# Power1.net
KiCad netlist of a schematic drawn in Altium Designer
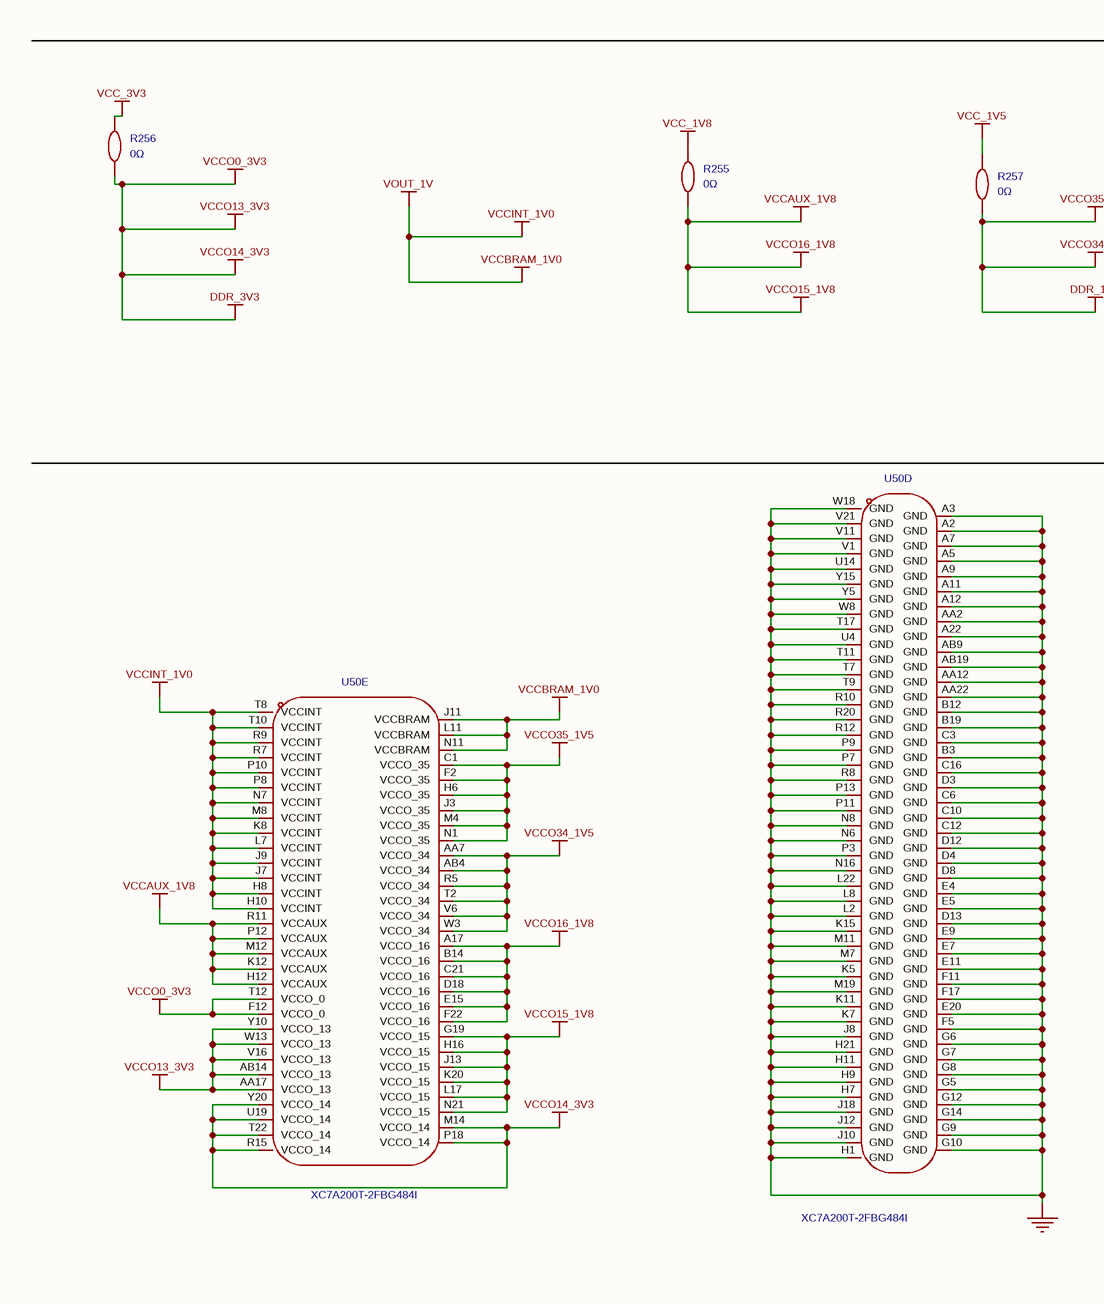
[diagram p0: Power1.schdoc, left]
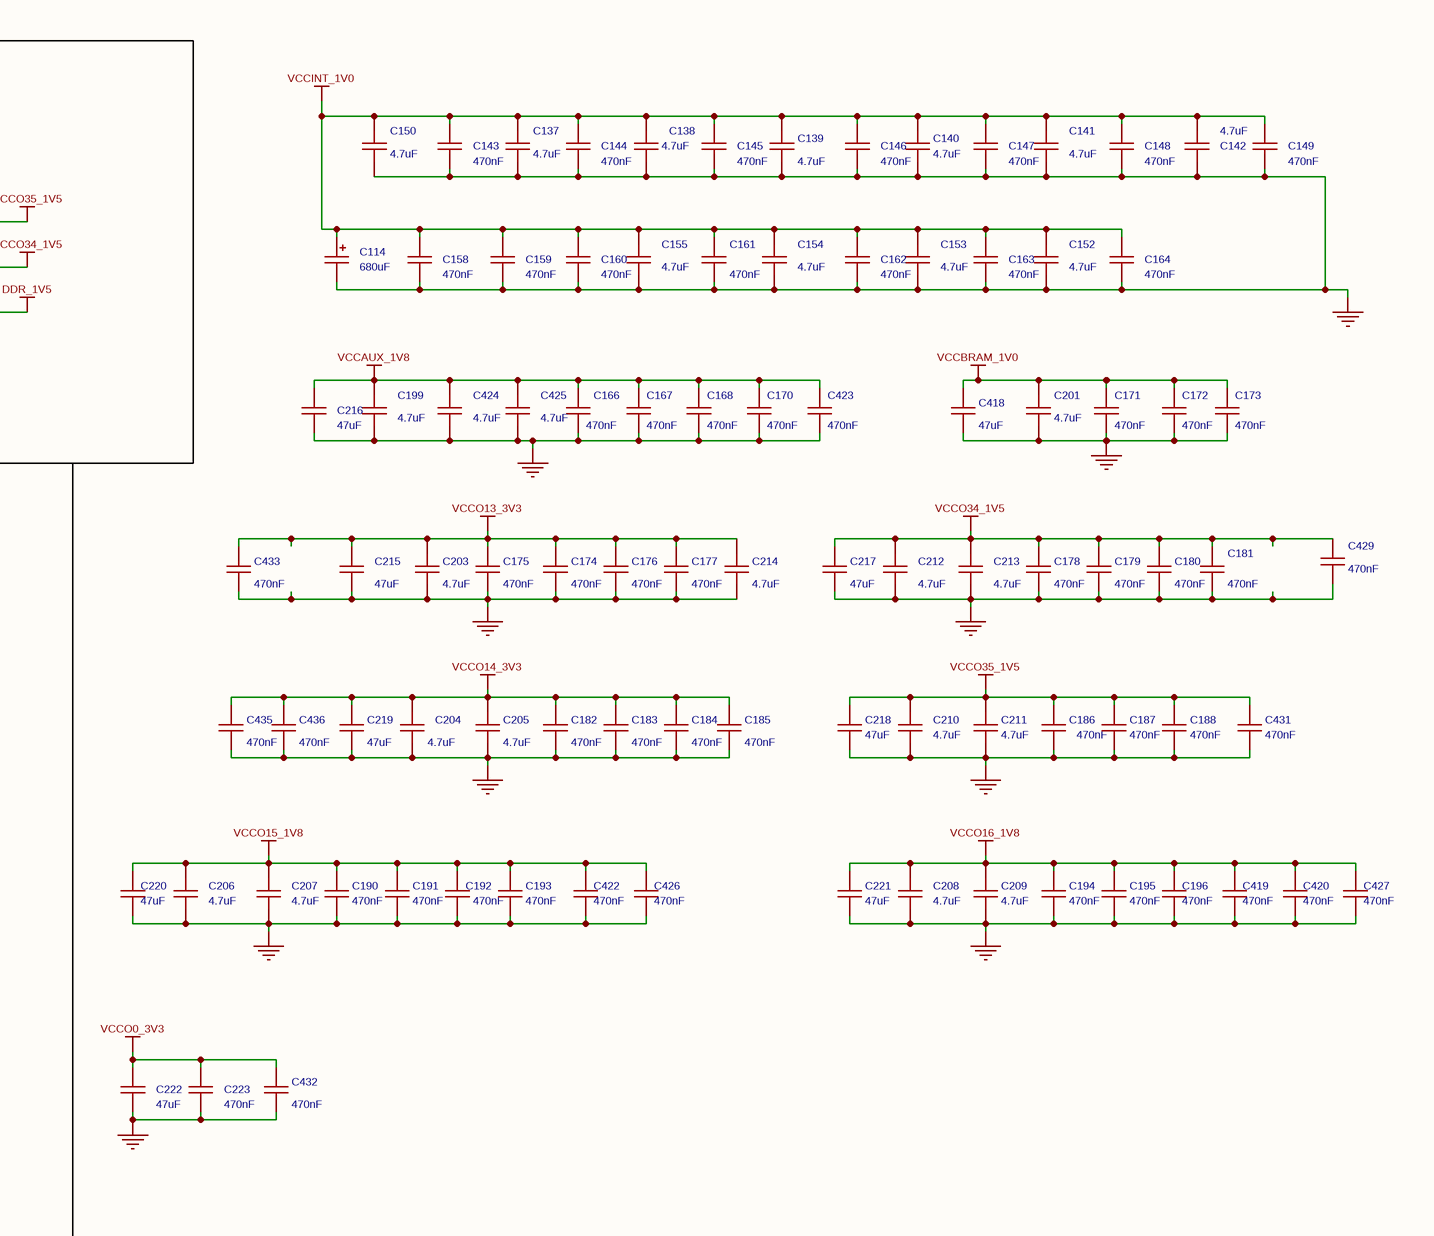
[diagram p1: Power1.schdoc, right]

(export (version "E")
  (design (tool "Eeschema 10.0.6"))
  (components
    (comp (ref "C114")
      (value "680uF")
      (footprint "CAP-SMD_L7.3-W4.3-R-RD")
      (description "容值:680uF;精度:±20%;额定电压:6.3V;等效串联电阻:18mΩ@100kHz;")
      (fields (field (name "MANUFACTURER") "PANASONIC(松下)") (field (name "MANUFACTURER PART") "6TPE680MI"))
      (libsource (lib "altium-import") (part "root_1_6TPE680MI_"))
    )
    (comp (ref "C137")
      (value "4.7uF")
      (footprint "C0402")
      (description "容值:4.7uF;精度:±20%;额定电压:6.3V;材质(温度系数):X5R;")
      (fields (field (name "MANUFACTURER") "SAMSUNG(三星)") (field (name "MANUFACTURERPART") "CL05A475MQ5NRNC"))
      (libsource (lib "altium-import") (part "root_0_CL05A475MQ5NRNC_"))
    )
    (comp (ref "C138")
      (value "4.7uF")
      (footprint "C0402")
      (description "容值:4.7uF;精度:±20%;额定电压:6.3V;材质(温度系数):X5R;")
      (fields (field (name "MANUFACTURER") "SAMSUNG(三星)") (field (name "MANUFACTURERPART") "CL05A475MQ5NRNC"))
      (libsource (lib "altium-import") (part "root_0_CL05A475MQ5NRNC_"))
    )
    (comp (ref "C139")
      (value "4.7uF")
      (footprint "C0402")
      (description "容值:4.7uF;精度:±20%;额定电压:6.3V;材质(温度系数):X5R;")
      (fields (field (name "MANUFACTURER") "SAMSUNG(三星)") (field (name "MANUFACTURERPART") "CL05A475MQ5NRNC"))
      (libsource (lib "altium-import") (part "root_0_CL05A475MQ5NRNC_"))
    )
    (comp (ref "C140")
      (value "4.7uF")
      (footprint "C0402")
      (description "容值:4.7uF;精度:±20%;额定电压:6.3V;材质(温度系数):X5R;")
      (fields (field (name "MANUFACTURER") "SAMSUNG(三星)") (field (name "MANUFACTURERPART") "CL05A475MQ5NRNC"))
      (libsource (lib "altium-import") (part "root_0_CL05A475MQ5NRNC_"))
    )
    (comp (ref "C141")
      (value "4.7uF")
      (footprint "C0402")
      (description "容值:4.7uF;精度:±20%;额定电压:6.3V;材质(温度系数):X5R;")
      (fields (field (name "MANUFACTURER") "SAMSUNG(三星)") (field (name "MANUFACTURERPART") "CL05A475MQ5NRNC"))
      (libsource (lib "altium-import") (part "root_0_CL05A475MQ5NRNC_"))
    )
    (comp (ref "C142")
      (value "4.7uF")
      (footprint "C0402")
      (description "容值:4.7uF;精度:±20%;额定电压:6.3V;材质(温度系数):X5R;")
      (fields (field (name "MANUFACTURER") "SAMSUNG(三星)") (field (name "MANUFACTURERPART") "CL05A475MQ5NRNC"))
      (libsource (lib "altium-import") (part "root_0_CL05A475MQ5NRNC_"))
    )
    (comp (ref "C143")
      (value "470nF")
      (footprint "C0402")
      (description "容值:470nF;精度:±10%;额定电压:10V;材质(温度系数):X5R;")
      (fields (field (name "MANUFACTURER") "SAMSUNG(三星)") (field (name "MANUFACTURERPART") "CL05A474KP5NNNC"))
      (libsource (lib "altium-import") (part "root_1_CL05A474KP5NNNC_"))
    )
    (comp (ref "C144")
      (value "470nF")
      (footprint "C0402")
      (description "容值:470nF;精度:±10%;额定电压:10V;材质(温度系数):X5R;")
      (fields (field (name "MANUFACTURER") "SAMSUNG(三星)") (field (name "MANUFACTURERPART") "CL05A474KP5NNNC"))
      (libsource (lib "altium-import") (part "root_1_CL05A474KP5NNNC_"))
    )
    (comp (ref "C145")
      (value "470nF")
      (footprint "C0402")
      (description "容值:470nF;精度:±10%;额定电压:10V;材质(温度系数):X5R;")
      (fields (field (name "MANUFACTURER") "SAMSUNG(三星)") (field (name "MANUFACTURERPART") "CL05A474KP5NNNC"))
      (libsource (lib "altium-import") (part "root_1_CL05A474KP5NNNC_"))
    )
    (comp (ref "C146")
      (value "470nF")
      (footprint "C0402")
      (description "容值:470nF;精度:±10%;额定电压:10V;材质(温度系数):X5R;")
      (fields (field (name "MANUFACTURER") "SAMSUNG(三星)") (field (name "MANUFACTURERPART") "CL05A474KP5NNNC"))
      (libsource (lib "altium-import") (part "root_1_CL05A474KP5NNNC_"))
    )
    (comp (ref "C147")
      (value "470nF")
      (footprint "C0402")
      (description "容值:470nF;精度:±10%;额定电压:10V;材质(温度系数):X5R;")
      (fields (field (name "MANUFACTURER") "SAMSUNG(三星)") (field (name "MANUFACTURERPART") "CL05A474KP5NNNC"))
      (libsource (lib "altium-import") (part "root_1_CL05A474KP5NNNC_"))
    )
    (comp (ref "C148")
      (value "470nF")
      (footprint "C0402")
      (description "容值:470nF;精度:±10%;额定电压:10V;材质(温度系数):X5R;")
      (fields (field (name "MANUFACTURER") "SAMSUNG(三星)") (field (name "MANUFACTURERPART") "CL05A474KP5NNNC"))
      (libsource (lib "altium-import") (part "root_1_CL05A474KP5NNNC_"))
    )
    (comp (ref "C149")
      (value "470nF")
      (footprint "C0402")
      (description "容值:470nF;精度:±10%;额定电压:10V;材质(温度系数):X5R;")
      (fields (field (name "MANUFACTURER") "SAMSUNG(三星)") (field (name "MANUFACTURERPART") "CL05A474KP5NNNC"))
      (libsource (lib "altium-import") (part "root_1_CL05A474KP5NNNC_"))
    )
    (comp (ref "C150")
      (value "4.7uF")
      (footprint "C0402")
      (description "容值:4.7uF;精度:±20%;额定电压:6.3V;材质(温度系数):X5R;")
      (fields (field (name "MANUFACTURER") "SAMSUNG(三星)") (field (name "MANUFACTURERPART") "CL05A475MQ5NRNC"))
      (libsource (lib "altium-import") (part "root_0_CL05A475MQ5NRNC_"))
    )
    (comp (ref "C152")
      (value "4.7uF")
      (footprint "C0402")
      (description "容值:4.7uF;精度:±20%;额定电压:6.3V;材质(温度系数):X5R;")
      (fields (field (name "MANUFACTURER") "SAMSUNG(三星)") (field (name "MANUFACTURERPART") "CL05A475MQ5NRNC"))
      (libsource (lib "altium-import") (part "root_0_CL05A475MQ5NRNC_"))
    )
    (comp (ref "C153")
      (value "4.7uF")
      (footprint "C0402")
      (description "容值:4.7uF;精度:±20%;额定电压:6.3V;材质(温度系数):X5R;")
      (fields (field (name "MANUFACTURER") "SAMSUNG(三星)") (field (name "MANUFACTURERPART") "CL05A475MQ5NRNC"))
      (libsource (lib "altium-import") (part "root_0_CL05A475MQ5NRNC_"))
    )
    (comp (ref "C154")
      (value "4.7uF")
      (footprint "C0402")
      (description "容值:4.7uF;精度:±20%;额定电压:6.3V;材质(温度系数):X5R;")
      (fields (field (name "MANUFACTURER") "SAMSUNG(三星)") (field (name "MANUFACTURERPART") "CL05A475MQ5NRNC"))
      (libsource (lib "altium-import") (part "root_0_CL05A475MQ5NRNC_"))
    )
    (comp (ref "C155")
      (value "4.7uF")
      (footprint "C0402")
      (description "容值:4.7uF;精度:±20%;额定电压:6.3V;材质(温度系数):X5R;")
      (fields (field (name "MANUFACTURER") "SAMSUNG(三星)") (field (name "MANUFACTURERPART") "CL05A475MQ5NRNC"))
      (libsource (lib "altium-import") (part "root_0_CL05A475MQ5NRNC_"))
    )
    (comp (ref "C158")
      (value "470nF")
      (footprint "C0402")
      (description "容值:470nF;精度:±10%;额定电压:10V;材质(温度系数):X5R;")
      (fields (field (name "MANUFACTURER") "SAMSUNG(三星)") (field (name "MANUFACTURERPART") "CL05A474KP5NNNC"))
      (libsource (lib "altium-import") (part "root_1_CL05A474KP5NNNC_"))
    )
    (comp (ref "C159")
      (value "470nF")
      (footprint "C0402")
      (description "容值:470nF;精度:±10%;额定电压:10V;材质(温度系数):X5R;")
      (fields (field (name "MANUFACTURER") "SAMSUNG(三星)") (field (name "MANUFACTURERPART") "CL05A474KP5NNNC"))
      (libsource (lib "altium-import") (part "root_1_CL05A474KP5NNNC_"))
    )
    (comp (ref "C160")
      (value "470nF")
      (footprint "C0402")
      (description "容值:470nF;精度:±10%;额定电压:10V;材质(温度系数):X5R;")
      (fields (field (name "MANUFACTURER") "SAMSUNG(三星)") (field (name "MANUFACTURERPART") "CL05A474KP5NNNC"))
      (libsource (lib "altium-import") (part "root_1_CL05A474KP5NNNC_"))
    )
    (comp (ref "C161")
      (value "470nF")
      (footprint "C0402")
      (description "容值:470nF;精度:±10%;额定电压:10V;材质(温度系数):X5R;")
      (fields (field (name "MANUFACTURER") "SAMSUNG(三星)") (field (name "MANUFACTURERPART") "CL05A474KP5NNNC"))
      (libsource (lib "altium-import") (part "root_1_CL05A474KP5NNNC_"))
    )
    (comp (ref "C162")
      (value "470nF")
      (footprint "C0402")
      (description "容值:470nF;精度:±10%;额定电压:10V;材质(温度系数):X5R;")
      (fields (field (name "MANUFACTURER") "SAMSUNG(三星)") (field (name "MANUFACTURERPART") "CL05A474KP5NNNC"))
      (libsource (lib "altium-import") (part "root_1_CL05A474KP5NNNC_"))
    )
    (comp (ref "C163")
      (value "470nF")
      (footprint "C0402")
      (description "容值:470nF;精度:±10%;额定电压:10V;材质(温度系数):X5R;")
      (fields (field (name "MANUFACTURER") "SAMSUNG(三星)") (field (name "MANUFACTURERPART") "CL05A474KP5NNNC"))
      (libsource (lib "altium-import") (part "root_1_CL05A474KP5NNNC_"))
    )
    (comp (ref "C164")
      (value "470nF")
      (footprint "C0402")
      (description "容值:470nF;精度:±10%;额定电压:10V;材质(温度系数):X5R;")
      (fields (field (name "MANUFACTURER") "SAMSUNG(三星)") (field (name "MANUFACTURERPART") "CL05A474KP5NNNC"))
      (libsource (lib "altium-import") (part "root_1_CL05A474KP5NNNC_"))
    )
    (comp (ref "C166")
      (value "470nF")
      (footprint "C0402")
      (description "容值:470nF;精度:±10%;额定电压:10V;材质(温度系数):X5R;")
      (fields (field (name "MANUFACTURER") "SAMSUNG(三星)") (field (name "MANUFACTURERPART") "CL05A474KP5NNNC"))
      (libsource (lib "altium-import") (part "root_1_CL05A474KP5NNNC_"))
    )
    (comp (ref "C167")
      (value "470nF")
      (footprint "C0402")
      (description "容值:470nF;精度:±10%;额定电压:10V;材质(温度系数):X5R;")
      (fields (field (name "MANUFACTURER") "SAMSUNG(三星)") (field (name "MANUFACTURERPART") "CL05A474KP5NNNC"))
      (libsource (lib "altium-import") (part "root_1_CL05A474KP5NNNC_"))
    )
    (comp (ref "C168")
      (value "470nF")
      (footprint "C0402")
      (description "容值:470nF;精度:±10%;额定电压:10V;材质(温度系数):X5R;")
      (fields (field (name "MANUFACTURER") "SAMSUNG(三星)") (field (name "MANUFACTURERPART") "CL05A474KP5NNNC"))
      (libsource (lib "altium-import") (part "root_1_CL05A474KP5NNNC_"))
    )
    (comp (ref "C170")
      (value "470nF")
      (footprint "C0402")
      (description "容值:470nF;精度:±10%;额定电压:10V;材质(温度系数):X5R;")
      (fields (field (name "MANUFACTURER") "SAMSUNG(三星)") (field (name "MANUFACTURERPART") "CL05A474KP5NNNC"))
      (libsource (lib "altium-import") (part "root_1_CL05A474KP5NNNC_"))
    )
    (comp (ref "C171")
      (value "470nF")
      (footprint "C0402")
      (description "容值:470nF;精度:±10%;额定电压:10V;材质(温度系数):X5R;")
      (fields (field (name "MANUFACTURER") "SAMSUNG(三星)") (field (name "MANUFACTURERPART") "CL05A474KP5NNNC"))
      (libsource (lib "altium-import") (part "root_1_CL05A474KP5NNNC_"))
    )
    (comp (ref "C172")
      (value "470nF")
      (footprint "C0402")
      (description "容值:470nF;精度:±10%;额定电压:10V;材质(温度系数):X5R;")
      (fields (field (name "MANUFACTURER") "SAMSUNG(三星)") (field (name "MANUFACTURERPART") "CL05A474KP5NNNC"))
      (libsource (lib "altium-import") (part "root_1_CL05A474KP5NNNC_"))
    )
    (comp (ref "C173")
      (value "470nF")
      (footprint "C0402")
      (description "容值:470nF;精度:±10%;额定电压:10V;材质(温度系数):X5R;")
      (fields (field (name "MANUFACTURER") "SAMSUNG(三星)") (field (name "MANUFACTURERPART") "CL05A474KP5NNNC"))
      (libsource (lib "altium-import") (part "root_1_CL05A474KP5NNNC_"))
    )
    (comp (ref "C174")
      (value "470nF")
      (footprint "C0402")
      (description "容值:470nF;精度:±10%;额定电压:10V;材质(温度系数):X5R;")
      (fields (field (name "MANUFACTURER") "SAMSUNG(三星)") (field (name "MANUFACTURERPART") "CL05A474KP5NNNC"))
      (libsource (lib "altium-import") (part "root_1_CL05A474KP5NNNC_"))
    )
    (comp (ref "C175")
      (value "470nF")
      (footprint "C0402")
      (description "容值:470nF;精度:±10%;额定电压:10V;材质(温度系数):X5R;")
      (fields (field (name "MANUFACTURER") "SAMSUNG(三星)") (field (name "MANUFACTURERPART") "CL05A474KP5NNNC"))
      (libsource (lib "altium-import") (part "root_1_CL05A474KP5NNNC_"))
    )
    (comp (ref "C176")
      (value "470nF")
      (footprint "C0402")
      (description "容值:470nF;精度:±10%;额定电压:10V;材质(温度系数):X5R;")
      (fields (field (name "MANUFACTURER") "SAMSUNG(三星)") (field (name "MANUFACTURERPART") "CL05A474KP5NNNC"))
      (libsource (lib "altium-import") (part "root_1_CL05A474KP5NNNC_"))
    )
    (comp (ref "C177")
      (value "470nF")
      (footprint "C0402")
      (description "容值:470nF;精度:±10%;额定电压:10V;材质(温度系数):X5R;")
      (fields (field (name "MANUFACTURER") "SAMSUNG(三星)") (field (name "MANUFACTURERPART") "CL05A474KP5NNNC"))
      (libsource (lib "altium-import") (part "root_1_CL05A474KP5NNNC_"))
    )
    (comp (ref "C178")
      (value "470nF")
      (footprint "C0402")
      (description "容值:470nF;精度:±10%;额定电压:10V;材质(温度系数):X5R;")
      (fields (field (name "MANUFACTURER") "SAMSUNG(三星)") (field (name "MANUFACTURERPART") "CL05A474KP5NNNC"))
      (libsource (lib "altium-import") (part "root_1_CL05A474KP5NNNC_"))
    )
    (comp (ref "C179")
      (value "470nF")
      (footprint "C0402")
      (description "容值:470nF;精度:±10%;额定电压:10V;材质(温度系数):X5R;")
      (fields (field (name "MANUFACTURER") "SAMSUNG(三星)") (field (name "MANUFACTURERPART") "CL05A474KP5NNNC"))
      (libsource (lib "altium-import") (part "root_1_CL05A474KP5NNNC_"))
    )
    (comp (ref "C180")
      (value "470nF")
      (footprint "C0402")
      (description "容值:470nF;精度:±10%;额定电压:10V;材质(温度系数):X5R;")
      (fields (field (name "MANUFACTURER") "SAMSUNG(三星)") (field (name "MANUFACTURERPART") "CL05A474KP5NNNC"))
      (libsource (lib "altium-import") (part "root_1_CL05A474KP5NNNC_"))
    )
    (comp (ref "C181")
      (value "470nF")
      (footprint "C0402")
      (description "容值:470nF;精度:±10%;额定电压:10V;材质(温度系数):X5R;")
      (fields (field (name "MANUFACTURER") "SAMSUNG(三星)") (field (name "MANUFACTURERPART") "CL05A474KP5NNNC"))
      (libsource (lib "altium-import") (part "root_1_CL05A474KP5NNNC_"))
    )
    (comp (ref "C182")
      (value "470nF")
      (footprint "C0402")
      (description "容值:470nF;精度:±10%;额定电压:10V;材质(温度系数):X5R;")
      (fields (field (name "MANUFACTURER") "SAMSUNG(三星)") (field (name "MANUFACTURERPART") "CL05A474KP5NNNC"))
      (libsource (lib "altium-import") (part "root_1_CL05A474KP5NNNC_"))
    )
    (comp (ref "C183")
      (value "470nF")
      (footprint "C0402")
      (description "容值:470nF;精度:±10%;额定电压:10V;材质(温度系数):X5R;")
      (fields (field (name "MANUFACTURER") "SAMSUNG(三星)") (field (name "MANUFACTURERPART") "CL05A474KP5NNNC"))
      (libsource (lib "altium-import") (part "root_1_CL05A474KP5NNNC_"))
    )
    (comp (ref "C184")
      (value "470nF")
      (footprint "C0402")
      (description "容值:470nF;精度:±10%;额定电压:10V;材质(温度系数):X5R;")
      (fields (field (name "MANUFACTURER") "SAMSUNG(三星)") (field (name "MANUFACTURERPART") "CL05A474KP5NNNC"))
      (libsource (lib "altium-import") (part "root_1_CL05A474KP5NNNC_"))
    )
    (comp (ref "C185")
      (value "470nF")
      (footprint "C0402")
      (description "容值:470nF;精度:±10%;额定电压:10V;材质(温度系数):X5R;")
      (fields (field (name "MANUFACTURER") "SAMSUNG(三星)") (field (name "MANUFACTURERPART") "CL05A474KP5NNNC"))
      (libsource (lib "altium-import") (part "root_1_CL05A474KP5NNNC_"))
    )
    (comp (ref "C186")
      (value "470nF")
      (footprint "C0402")
      (description "容值:470nF;精度:±10%;额定电压:10V;材质(温度系数):X5R;")
      (fields (field (name "MANUFACTURER") "SAMSUNG(三星)") (field (name "MANUFACTURERPART") "CL05A474KP5NNNC"))
      (libsource (lib "altium-import") (part "root_1_CL05A474KP5NNNC_"))
    )
    (comp (ref "C187")
      (value "470nF")
      (footprint "C0402")
      (description "容值:470nF;精度:±10%;额定电压:10V;材质(温度系数):X5R;")
      (fields (field (name "MANUFACTURER") "SAMSUNG(三星)") (field (name "MANUFACTURERPART") "CL05A474KP5NNNC"))
      (libsource (lib "altium-import") (part "root_1_CL05A474KP5NNNC_"))
    )
    (comp (ref "C188")
      (value "470nF")
      (footprint "C0402")
      (description "容值:470nF;精度:±10%;额定电压:10V;材质(温度系数):X5R;")
      (fields (field (name "MANUFACTURER") "SAMSUNG(三星)") (field (name "MANUFACTURERPART") "CL05A474KP5NNNC"))
      (libsource (lib "altium-import") (part "root_1_CL05A474KP5NNNC_"))
    )
    (comp (ref "C190")
      (value "470nF")
      (footprint "C0402")
      (description "容值:470nF;精度:±10%;额定电压:10V;材质(温度系数):X5R;")
      (fields (field (name "MANUFACTURER") "SAMSUNG(三星)") (field (name "MANUFACTURERPART") "CL05A474KP5NNNC"))
      (libsource (lib "altium-import") (part "root_1_CL05A474KP5NNNC_"))
    )
    (comp (ref "C191")
      (value "470nF")
      (footprint "C0402")
      (description "容值:470nF;精度:±10%;额定电压:10V;材质(温度系数):X5R;")
      (fields (field (name "MANUFACTURER") "SAMSUNG(三星)") (field (name "MANUFACTURERPART") "CL05A474KP5NNNC"))
      (libsource (lib "altium-import") (part "root_1_CL05A474KP5NNNC_"))
    )
    (comp (ref "C192")
      (value "470nF")
      (footprint "C0402")
      (description "容值:470nF;精度:±10%;额定电压:10V;材质(温度系数):X5R;")
      (fields (field (name "MANUFACTURER") "SAMSUNG(三星)") (field (name "MANUFACTURERPART") "CL05A474KP5NNNC"))
      (libsource (lib "altium-import") (part "root_1_CL05A474KP5NNNC_"))
    )
    (comp (ref "C193")
      (value "470nF")
      (footprint "C0402")
      (description "容值:470nF;精度:±10%;额定电压:10V;材质(温度系数):X5R;")
      (fields (field (name "MANUFACTURER") "SAMSUNG(三星)") (field (name "MANUFACTURERPART") "CL05A474KP5NNNC"))
      (libsource (lib "altium-import") (part "root_1_CL05A474KP5NNNC_"))
    )
    (comp (ref "C194")
      (value "470nF")
      (footprint "C0402")
      (description "容值:470nF;精度:±10%;额定电压:10V;材质(温度系数):X5R;")
      (fields (field (name "MANUFACTURER") "SAMSUNG(三星)") (field (name "MANUFACTURERPART") "CL05A474KP5NNNC"))
      (libsource (lib "altium-import") (part "root_1_CL05A474KP5NNNC_"))
    )
    (comp (ref "C195")
      (value "470nF")
      (footprint "C0402")
      (description "容值:470nF;精度:±10%;额定电压:10V;材质(温度系数):X5R;")
      (fields (field (name "MANUFACTURER") "SAMSUNG(三星)") (field (name "MANUFACTURERPART") "CL05A474KP5NNNC"))
      (libsource (lib "altium-import") (part "root_1_CL05A474KP5NNNC_"))
    )
    (comp (ref "C196")
      (value "470nF")
      (footprint "C0402")
      (description "容值:470nF;精度:±10%;额定电压:10V;材质(温度系数):X5R;")
      (fields (field (name "MANUFACTURER") "SAMSUNG(三星)") (field (name "MANUFACTURERPART") "CL05A474KP5NNNC"))
      (libsource (lib "altium-import") (part "root_1_CL05A474KP5NNNC_"))
    )
    (comp (ref "C199")
      (value "4.7uF")
      (footprint "C0402")
      (description "容值:4.7uF;精度:±20%;额定电压:6.3V;材质(温度系数):X5R;")
      (fields (field (name "MANUFACTURER") "SAMSUNG(三星)") (field (name "MANUFACTURERPART") "CL05A475MQ5NRNC"))
      (libsource (lib "altium-import") (part "root_0_CL05A475MQ5NRNC_"))
    )
    (comp (ref "C201")
      (value "4.7uF")
      (footprint "C0402")
      (description "容值:4.7uF;精度:±20%;额定电压:6.3V;材质(温度系数):X5R;")
      (fields (field (name "MANUFACTURER") "SAMSUNG(三星)") (field (name "MANUFACTURERPART") "CL05A475MQ5NRNC"))
      (libsource (lib "altium-import") (part "root_0_CL05A475MQ5NRNC_"))
    )
    (comp (ref "C203")
      (value "4.7uF")
      (footprint "C0402")
      (description "容值:4.7uF;精度:±20%;额定电压:6.3V;材质(温度系数):X5R;")
      (fields (field (name "MANUFACTURER") "SAMSUNG(三星)") (field (name "MANUFACTURERPART") "CL05A475MQ5NRNC"))
      (libsource (lib "altium-import") (part "root_0_CL05A475MQ5NRNC_"))
    )
    (comp (ref "C204")
      (value "4.7uF")
      (footprint "C0402")
      (description "容值:4.7uF;精度:±20%;额定电压:6.3V;材质(温度系数):X5R;")
      (fields (field (name "MANUFACTURER") "SAMSUNG(三星)") (field (name "MANUFACTURERPART") "CL05A475MQ5NRNC"))
      (libsource (lib "altium-import") (part "root_0_CL05A475MQ5NRNC_"))
    )
    (comp (ref "C205")
      (value "4.7uF")
      (footprint "C0402")
      (description "容值:4.7uF;精度:±20%;额定电压:6.3V;材质(温度系数):X5R;")
      (fields (field (name "MANUFACTURER") "SAMSUNG(三星)") (field (name "MANUFACTURERPART") "CL05A475MQ5NRNC"))
      (libsource (lib "altium-import") (part "root_0_CL05A475MQ5NRNC_"))
    )
    (comp (ref "C206")
      (value "4.7uF")
      (footprint "C0402")
      (description "容值:4.7uF;精度:±20%;额定电压:6.3V;材质(温度系数):X5R;")
      (fields (field (name "MANUFACTURER") "SAMSUNG(三星)") (field (name "MANUFACTURERPART") "CL05A475MQ5NRNC"))
      (libsource (lib "altium-import") (part "root_0_CL05A475MQ5NRNC_"))
    )
    (comp (ref "C207")
      (value "4.7uF")
      (footprint "C0402")
      (description "容值:4.7uF;精度:±20%;额定电压:6.3V;材质(温度系数):X5R;")
      (fields (field (name "MANUFACTURER") "SAMSUNG(三星)") (field (name "MANUFACTURERPART") "CL05A475MQ5NRNC"))
      (libsource (lib "altium-import") (part "root_0_CL05A475MQ5NRNC_"))
    )
    (comp (ref "C208")
      (value "4.7uF")
      (footprint "C0402")
      (description "容值:4.7uF;精度:±20%;额定电压:6.3V;材质(温度系数):X5R;")
      (fields (field (name "MANUFACTURER") "SAMSUNG(三星)") (field (name "MANUFACTURERPART") "CL05A475MQ5NRNC"))
      (libsource (lib "altium-import") (part "root_0_CL05A475MQ5NRNC_"))
    )
    (comp (ref "C209")
      (value "4.7uF")
      (footprint "C0402")
      (description "容值:4.7uF;精度:±20%;额定电压:6.3V;材质(温度系数):X5R;")
      (fields (field (name "MANUFACTURER") "SAMSUNG(三星)") (field (name "MANUFACTURERPART") "CL05A475MQ5NRNC"))
      (libsource (lib "altium-import") (part "root_0_CL05A475MQ5NRNC_"))
    )
    (comp (ref "C210")
      (value "4.7uF")
      (footprint "C0402")
      (description "容值:4.7uF;精度:±20%;额定电压:6.3V;材质(温度系数):X5R;")
      (fields (field (name "MANUFACTURER") "SAMSUNG(三星)") (field (name "MANUFACTURERPART") "CL05A475MQ5NRNC"))
      (libsource (lib "altium-import") (part "root_0_CL05A475MQ5NRNC_"))
    )
    (comp (ref "C211")
      (value "4.7uF")
      (footprint "C0402")
      (description "容值:4.7uF;精度:±20%;额定电压:6.3V;材质(温度系数):X5R;")
      (fields (field (name "MANUFACTURER") "SAMSUNG(三星)") (field (name "MANUFACTURERPART") "CL05A475MQ5NRNC"))
      (libsource (lib "altium-import") (part "root_0_CL05A475MQ5NRNC_"))
    )
    (comp (ref "C212")
      (value "4.7uF")
      (footprint "C0402")
      (description "容值:4.7uF;精度:±20%;额定电压:6.3V;材质(温度系数):X5R;")
      (fields (field (name "MANUFACTURER") "SAMSUNG(三星)") (field (name "MANUFACTURERPART") "CL05A475MQ5NRNC"))
      (libsource (lib "altium-import") (part "root_0_CL05A475MQ5NRNC_"))
    )
    (comp (ref "C213")
      (value "4.7uF")
      (footprint "C0402")
      (description "容值:4.7uF;精度:±20%;额定电压:6.3V;材质(温度系数):X5R;")
      (fields (field (name "MANUFACTURER") "SAMSUNG(三星)") (field (name "MANUFACTURERPART") "CL05A475MQ5NRNC"))
      (libsource (lib "altium-import") (part "root_0_CL05A475MQ5NRNC_"))
    )
    (comp (ref "C214")
      (value "4.7uF")
      (footprint "C0402")
      (description "容值:4.7uF;精度:±20%;额定电压:6.3V;材质(温度系数):X5R;")
      (fields (field (name "MANUFACTURER") "SAMSUNG(三星)") (field (name "MANUFACTURERPART") "CL05A475MQ5NRNC"))
      (libsource (lib "altium-import") (part "root_0_CL05A475MQ5NRNC_"))
    )
    (comp (ref "C215")
      (value "47uF")
      (footprint "C0603")
      (description "容值:47uF;精度:±20%;额定电压:6.3V;材质(温度系数):X5R;")
      (fields
        (field (name "MANUFACTURER") "muRata(村田)")
        (field (name "MANUFACTURER PART") "GRM188R60J476ME15D")
      )
      (libsource (lib "altium-import") (part "root_1_GRM188R60J476ME15D_"))
    )
    (comp (ref "C216")
      (value "47uF")
      (footprint "C0603")
      (description "容值:47uF;精度:±20%;额定电压:6.3V;材质(温度系数):X5R;")
      (fields
        (field (name "MANUFACTURER") "muRata(村田)")
        (field (name "MANUFACTURER PART") "GRM188R60J476ME15D")
      )
      (libsource (lib "altium-import") (part "root_1_GRM188R60J476ME15D_"))
    )
    (comp (ref "C217")
      (value "47uF")
      (footprint "C0603")
      (description "容值:47uF;精度:±20%;额定电压:6.3V;材质(温度系数):X5R;")
      (fields
        (field (name "MANUFACTURER") "muRata(村田)")
        (field (name "MANUFACTURER PART") "GRM188R60J476ME15D")
      )
      (libsource (lib "altium-import") (part "root_1_GRM188R60J476ME15D_"))
    )
    (comp (ref "C218")
      (value "47uF")
      (footprint "C0603")
      (description "容值:47uF;精度:±20%;额定电压:6.3V;材质(温度系数):X5R;")
      (fields
        (field (name "MANUFACTURER") "muRata(村田)")
        (field (name "MANUFACTURER PART") "GRM188R60J476ME15D")
      )
      (libsource (lib "altium-import") (part "root_1_GRM188R60J476ME15D_"))
    )
    (comp (ref "C219")
      (value "47uF")
      (footprint "C0603")
      (description "容值:47uF;精度:±20%;额定电压:6.3V;材质(温度系数):X5R;")
      (fields
        (field (name "MANUFACTURER") "muRata(村田)")
        (field (name "MANUFACTURER PART") "GRM188R60J476ME15D")
      )
      (libsource (lib "altium-import") (part "root_1_GRM188R60J476ME15D_"))
    )
    (comp (ref "C220")
      (value "47uF")
      (footprint "C0603")
      (description "容值:47uF;精度:±20%;额定电压:6.3V;材质(温度系数):X5R;")
      (fields
        (field (name "MANUFACTURER") "muRata(村田)")
        (field (name "MANUFACTURER PART") "GRM188R60J476ME15D")
      )
      (libsource (lib "altium-import") (part "root_1_GRM188R60J476ME15D_"))
    )
    (comp (ref "C221")
      (value "47uF")
      (footprint "C0603")
      (description "容值:47uF;精度:±20%;额定电压:6.3V;材质(温度系数):X5R;")
      (fields
        (field (name "MANUFACTURER") "muRata(村田)")
        (field (name "MANUFACTURER PART") "GRM188R60J476ME15D")
      )
      (libsource (lib "altium-import") (part "root_1_GRM188R60J476ME15D_"))
    )
    (comp (ref "C222")
      (value "47uF")
      (footprint "C0603")
      (description "容值:47uF;精度:±20%;额定电压:6.3V;材质(温度系数):X5R;")
      (fields
        (field (name "MANUFACTURER") "muRata(村田)")
        (field (name "MANUFACTURER PART") "GRM188R60J476ME15D")
      )
      (libsource (lib "altium-import") (part "root_1_GRM188R60J476ME15D_"))
    )
    (comp (ref "C223")
      (value "470nF")
      (footprint "C0402")
      (description "容值:470nF;精度:±10%;额定电压:10V;材质(温度系数):X5R;")
      (fields (field (name "MANUFACTURER") "SAMSUNG(三星)") (field (name "MANUFACTURERPART") "CL05A474KP5NNNC"))
      (libsource (lib "altium-import") (part "root_1_CL05A474KP5NNNC_"))
    )
    (comp (ref "C418")
      (value "47uF")
      (footprint "C0603")
      (description "容值:47uF;精度:±20%;额定电压:6.3V;材质(温度系数):X5R;")
      (fields
        (field (name "MANUFACTURER") "muRata(村田)")
        (field (name "MANUFACTURER PART") "GRM188R60J476ME15D")
      )
      (libsource (lib "altium-import") (part "root_1_GRM188R60J476ME15D_"))
    )
    (comp (ref "C419")
      (value "470nF")
      (footprint "C0402")
      (description "容值:470nF;精度:±10%;额定电压:10V;材质(温度系数):X5R;")
      (fields (field (name "MANUFACTURER") "SAMSUNG(三星)") (field (name "MANUFACTURERPART") "CL05A474KP5NNNC"))
      (libsource (lib "altium-import") (part "root_1_CL05A474KP5NNNC_"))
    )
    (comp (ref "C420")
      (value "470nF")
      (footprint "C0402")
      (description "容值:470nF;精度:±10%;额定电压:10V;材质(温度系数):X5R;")
      (fields (field (name "MANUFACTURER") "SAMSUNG(三星)") (field (name "MANUFACTURERPART") "CL05A474KP5NNNC"))
      (libsource (lib "altium-import") (part "root_1_CL05A474KP5NNNC_"))
    )
    (comp (ref "C422")
      (value "470nF")
      (footprint "C0402")
      (description "容值:470nF;精度:±10%;额定电压:10V;材质(温度系数):X5R;")
      (fields (field (name "MANUFACTURER") "SAMSUNG(三星)") (field (name "MANUFACTURERPART") "CL05A474KP5NNNC"))
      (libsource (lib "altium-import") (part "root_1_CL05A474KP5NNNC_"))
    )
    (comp (ref "C423")
      (value "470nF")
      (footprint "C0402")
      (description "容值:470nF;精度:±10%;额定电压:10V;材质(温度系数):X5R;")
      (fields (field (name "MANUFACTURER") "SAMSUNG(三星)") (field (name "MANUFACTURERPART") "CL05A474KP5NNNC"))
      (libsource (lib "altium-import") (part "root_1_CL05A474KP5NNNC_"))
    )
    (comp (ref "C424")
      (value "4.7uF")
      (footprint "C0402")
      (description "容值:4.7uF;精度:±20%;额定电压:6.3V;材质(温度系数):X5R;")
      (fields (field (name "MANUFACTURER") "SAMSUNG(三星)") (field (name "MANUFACTURERPART") "CL05A475MQ5NRNC"))
      (libsource (lib "altium-import") (part "root_0_CL05A475MQ5NRNC_"))
    )
    (comp (ref "C425")
      (value "4.7uF")
      (footprint "C0402")
      (description "容值:4.7uF;精度:±20%;额定电压:6.3V;材质(温度系数):X5R;")
      (fields (field (name "MANUFACTURER") "SAMSUNG(三星)") (field (name "MANUFACTURERPART") "CL05A475MQ5NRNC"))
      (libsource (lib "altium-import") (part "root_0_CL05A475MQ5NRNC_"))
    )
    (comp (ref "C426")
      (value "470nF")
      (footprint "C0402")
      (description "容值:470nF;精度:±10%;额定电压:10V;材质(温度系数):X5R;")
      (fields (field (name "MANUFACTURER") "SAMSUNG(三星)") (field (name "MANUFACTURERPART") "CL05A474KP5NNNC"))
      (libsource (lib "altium-import") (part "root_1_CL05A474KP5NNNC_"))
    )
    (comp (ref "C427")
      (value "470nF")
      (footprint "C0402")
      (description "容值:470nF;精度:±10%;额定电压:10V;材质(温度系数):X5R;")
      (fields (field (name "MANUFACTURER") "SAMSUNG(三星)") (field (name "MANUFACTURERPART") "CL05A474KP5NNNC"))
      (libsource (lib "altium-import") (part "root_1_CL05A474KP5NNNC_"))
    )
    (comp (ref "C429")
      (value "470nF")
      (footprint "C0402")
      (description "容值:470nF;精度:±10%;额定电压:10V;材质(温度系数):X5R;")
      (fields (field (name "MANUFACTURER") "SAMSUNG(三星)") (field (name "MANUFACTURERPART") "CL05A474KP5NNNC"))
      (libsource (lib "altium-import") (part "root_1_CL05A474KP5NNNC_"))
    )
    (comp (ref "C431")
      (value "470nF")
      (footprint "C0402")
      (description "容值:470nF;精度:±10%;额定电压:10V;材质(温度系数):X5R;")
      (fields (field (name "MANUFACTURER") "SAMSUNG(三星)") (field (name "MANUFACTURERPART") "CL05A474KP5NNNC"))
      (libsource (lib "altium-import") (part "root_1_CL05A474KP5NNNC_"))
    )
    (comp (ref "C432")
      (value "470nF")
      (footprint "C0402")
      (description "容值:470nF;精度:±10%;额定电压:10V;材质(温度系数):X5R;")
      (fields (field (name "MANUFACTURER") "SAMSUNG(三星)") (field (name "MANUFACTURERPART") "CL05A474KP5NNNC"))
      (libsource (lib "altium-import") (part "root_1_CL05A474KP5NNNC_"))
    )
    (comp (ref "C433")
      (value "470nF")
      (footprint "C0402")
      (description "容值:470nF;精度:±10%;额定电压:10V;材质(温度系数):X5R;")
      (fields (field (name "MANUFACTURER") "SAMSUNG(三星)") (field (name "MANUFACTURERPART") "CL05A474KP5NNNC"))
      (libsource (lib "altium-import") (part "root_1_CL05A474KP5NNNC_"))
    )
    (comp (ref "C435")
      (value "470nF")
      (footprint "C0402")
      (description "容值:470nF;精度:±10%;额定电压:10V;材质(温度系数):X5R;")
      (fields (field (name "MANUFACTURER") "SAMSUNG(三星)") (field (name "MANUFACTURERPART") "CL05A474KP5NNNC"))
      (libsource (lib "altium-import") (part "root_1_CL05A474KP5NNNC_"))
    )
    (comp (ref "C436")
      (value "470nF")
      (footprint "C0402")
      (description "容值:470nF;精度:±10%;额定电压:10V;材质(温度系数):X5R;")
      (fields (field (name "MANUFACTURER") "SAMSUNG(三星)") (field (name "MANUFACTURERPART") "CL05A474KP5NNNC"))
      (libsource (lib "altium-import") (part "root_1_CL05A474KP5NNNC_"))
    )
    (comp (ref "R255")
      (value "0Ω")
      (footprint "R0805")
      (description "电阻类型:厚膜电阻;阻值:0Ω;精度:±1%;功率:125mW;最大工作电压:150V;温度系数:±800ppm/℃;")
      (fields
        (field (name "MANUFACTURER") "UNI-ROYAL(厚声)")
        (field (name "MANUFACTURER PART") "0805W8F0000T5E")
      )
      (libsource (lib "altium-import") (part "root_1_0805W8F0000T5E_"))
    )
    (comp (ref "R256")
      (value "0Ω")
      (footprint "R0805")
      (description "电阻类型:厚膜电阻;阻值:0Ω;精度:±1%;功率:125mW;最大工作电压:150V;温度系数:±800ppm/℃;")
      (fields
        (field (name "MANUFACTURER") "UNI-ROYAL(厚声)")
        (field (name "MANUFACTURER PART") "0805W8F0000T5E")
      )
      (libsource (lib "altium-import") (part "root_1_0805W8F0000T5E_"))
    )
    (comp (ref "R257")
      (value "0Ω")
      (footprint "R0805")
      (description "电阻类型:厚膜电阻;阻值:0Ω;精度:±1%;功率:125mW;最大工作电压:150V;温度系数:±800ppm/℃;")
      (fields
        (field (name "MANUFACTURER") "UNI-ROYAL(厚声)")
        (field (name "MANUFACTURER PART") "0805W8F0000T5E")
      )
      (libsource (lib "altium-import") (part "root_1_0805W8F0000T5E_"))
    )
    (comp (ref "U50")
      (value "XC7A200T-2FBG484I")
      (footprint "FBGA-484_L23.0-W23.0-R22-C22-P1.00-TL")
      (fields (field (name "MANUFACTURER") "AMD/XILINX(赛灵思)"))
      (libsource (lib "altium-import") (part "root_0_XC7A200T-2FBG484I_"))
    )
  )
  (nets
    (net (code "1") (name "DDR_1V5") (class "Default")
      (node (ref "C178") (pin "2") (pinfunction "2_2") (pintype "passive"))
      (node (ref "C179") (pin "2") (pinfunction "2_2") (pintype "passive"))
      (node (ref "C180") (pin "2") (pinfunction "2_2") (pintype "passive"))
      (node (ref "C181") (pin "2") (pinfunction "2_2") (pintype "passive"))
      (node (ref "C186") (pin "2") (pinfunction "2_2") (pintype "passive"))
      (node (ref "C187") (pin "2") (pinfunction "2_2") (pintype "passive"))
      (node (ref "C188") (pin "2") (pinfunction "2_2") (pintype "passive"))
      (node (ref "C210") (pin "2") (pinfunction "2_2") (pintype "passive"))
      (node (ref "C211") (pin "2") (pinfunction "2_2") (pintype "passive"))
      (node (ref "C212") (pin "2") (pinfunction "2_2") (pintype "passive"))
      (node (ref "C213") (pin "2") (pinfunction "2_2") (pintype "passive"))
      (node (ref "C217") (pin "2") (pinfunction "2_2") (pintype "passive"))
      (node (ref "C218") (pin "2") (pinfunction "2_2") (pintype "passive"))
      (node (ref "C429") (pin "2") (pinfunction "2_2") (pintype "passive"))
      (node (ref "C431") (pin "2") (pinfunction "2_2") (pintype "passive"))
      (node (ref "R257") (pin "1") (pinfunction "1_1") (pintype "passive"))
      (node (ref "U50") (pin "AA7") (pinfunction "VCCO_34_AA7") (pintype "passive"))
      (node (ref "U50") (pin "AB4") (pinfunction "VCCO_34_AB4") (pintype "passive"))
      (node (ref "U50") (pin "C1") (pinfunction "VCCO_35_C1") (pintype "passive"))
      (node (ref "U50") (pin "F2") (pinfunction "VCCO_35_F2") (pintype "passive"))
      (node (ref "U50") (pin "H6") (pinfunction "VCCO_35_H6") (pintype "passive"))
      (node (ref "U50") (pin "J3") (pinfunction "VCCO_35_J3") (pintype "passive"))
      (node (ref "U50") (pin "M4") (pinfunction "VCCO_35_M4") (pintype "passive"))
      (node (ref "U50") (pin "N1") (pinfunction "VCCO_35_N1") (pintype "passive"))
      (node (ref "U50") (pin "R5") (pinfunction "VCCO_34_R5") (pintype "passive"))
      (node (ref "U50") (pin "T2") (pinfunction "VCCO_34_T2") (pintype "passive"))
      (node (ref "U50") (pin "V6") (pinfunction "VCCO_34_V6") (pintype "passive"))
      (node (ref "U50") (pin "W3") (pinfunction "VCCO_34_W3") (pintype "passive"))
    )
    (net (code "2") (name "DDR_3V3") (class "Default")
      (node (ref "C174") (pin "2") (pinfunction "2_2") (pintype "passive"))
      (node (ref "C175") (pin "2") (pinfunction "2_2") (pintype "passive"))
      (node (ref "C176") (pin "2") (pinfunction "2_2") (pintype "passive"))
      (node (ref "C177") (pin "2") (pinfunction "2_2") (pintype "passive"))
      (node (ref "C182") (pin "2") (pinfunction "2_2") (pintype "passive"))
      (node (ref "C183") (pin "2") (pinfunction "2_2") (pintype "passive"))
      (node (ref "C184") (pin "2") (pinfunction "2_2") (pintype "passive"))
      (node (ref "C185") (pin "2") (pinfunction "2_2") (pintype "passive"))
      (node (ref "C203") (pin "2") (pinfunction "2_2") (pintype "passive"))
      (node (ref "C204") (pin "2") (pinfunction "2_2") (pintype "passive"))
      (node (ref "C205") (pin "2") (pinfunction "2_2") (pintype "passive"))
      (node (ref "C214") (pin "2") (pinfunction "2_2") (pintype "passive"))
      (node (ref "C215") (pin "2") (pinfunction "2_2") (pintype "passive"))
      (node (ref "C219") (pin "2") (pinfunction "2_2") (pintype "passive"))
      (node (ref "C222") (pin "2") (pinfunction "2_2") (pintype "passive"))
      (node (ref "C223") (pin "2") (pinfunction "2_2") (pintype "passive"))
      (node (ref "C432") (pin "2") (pinfunction "2_2") (pintype "passive"))
      (node (ref "C433") (pin "2") (pinfunction "2_2") (pintype "passive"))
      (node (ref "C435") (pin "2") (pinfunction "2_2") (pintype "passive"))
      (node (ref "C436") (pin "2") (pinfunction "2_2") (pintype "passive"))
      (node (ref "R256") (pin "1") (pinfunction "1_1") (pintype "passive"))
      (node (ref "U50") (pin "AA17") (pinfunction "VCCO_13_AA17") (pintype "passive"))
      (node (ref "U50") (pin "AB14") (pinfunction "VCCO_13_AB14") (pintype "passive"))
      (node (ref "U50") (pin "F12") (pinfunction "VCCO_0_F12") (pintype "passive"))
      (node (ref "U50") (pin "M14") (pinfunction "VCCO_14_M14") (pintype "passive"))
      (node (ref "U50") (pin "P18") (pinfunction "VCCO_14_P18") (pintype "passive"))
      (node (ref "U50") (pin "R15") (pinfunction "VCCO_14_R15") (pintype "passive"))
      (node (ref "U50") (pin "T12") (pinfunction "VCCO_0_T12") (pintype "passive"))
      (node (ref "U50") (pin "T22") (pinfunction "VCCO_14_T22") (pintype "passive"))
      (node (ref "U50") (pin "U19") (pinfunction "VCCO_14_U19") (pintype "passive"))
      (node (ref "U50") (pin "V16") (pinfunction "VCCO_13_V16") (pintype "passive"))
      (node (ref "U50") (pin "W13") (pinfunction "VCCO_13_W13") (pintype "passive"))
      (node (ref "U50") (pin "Y10") (pinfunction "VCCO_13_Y10") (pintype "passive"))
      (node (ref "U50") (pin "Y20") (pinfunction "VCCO_14_Y20") (pintype "passive"))
    )
    (net (code "3") (name "GND") (class "Default")
      (node (ref "C114") (pin "2") (pinfunction "2_2") (pintype "passive"))
      (node (ref "C137") (pin "1") (pinfunction "1_1") (pintype "passive"))
      (node (ref "C138") (pin "1") (pinfunction "1_1") (pintype "passive"))
      (node (ref "C139") (pin "1") (pinfunction "1_1") (pintype "passive"))
      (node (ref "C140") (pin "1") (pinfunction "1_1") (pintype "passive"))
      (node (ref "C141") (pin "1") (pinfunction "1_1") (pintype "passive"))
      (node (ref "C142") (pin "1") (pinfunction "1_1") (pintype "passive"))
      (node (ref "C143") (pin "1") (pinfunction "1_1") (pintype "passive"))
      (node (ref "C144") (pin "1") (pinfunction "1_1") (pintype "passive"))
      (node (ref "C145") (pin "1") (pinfunction "1_1") (pintype "passive"))
      (node (ref "C146") (pin "1") (pinfunction "1_1") (pintype "passive"))
      (node (ref "C147") (pin "1") (pinfunction "1_1") (pintype "passive"))
      (node (ref "C148") (pin "1") (pinfunction "1_1") (pintype "passive"))
      (node (ref "C149") (pin "1") (pinfunction "1_1") (pintype "passive"))
      (node (ref "C150") (pin "1") (pinfunction "1_1") (pintype "passive"))
      (node (ref "C152") (pin "1") (pinfunction "1_1") (pintype "passive"))
      (node (ref "C153") (pin "1") (pinfunction "1_1") (pintype "passive"))
      (node (ref "C154") (pin "1") (pinfunction "1_1") (pintype "passive"))
      (node (ref "C155") (pin "1") (pinfunction "1_1") (pintype "passive"))
      (node (ref "C158") (pin "1") (pinfunction "1_1") (pintype "passive"))
      (node (ref "C159") (pin "1") (pinfunction "1_1") (pintype "passive"))
      (node (ref "C160") (pin "1") (pinfunction "1_1") (pintype "passive"))
      (node (ref "C161") (pin "1") (pinfunction "1_1") (pintype "passive"))
      (node (ref "C162") (pin "1") (pinfunction "1_1") (pintype "passive"))
      (node (ref "C163") (pin "1") (pinfunction "1_1") (pintype "passive"))
      (node (ref "C164") (pin "1") (pinfunction "1_1") (pintype "passive"))
      (node (ref "C166") (pin "1") (pinfunction "1_1") (pintype "passive"))
      (node (ref "C167") (pin "1") (pinfunction "1_1") (pintype "passive"))
      (node (ref "C168") (pin "1") (pinfunction "1_1") (pintype "passive"))
      (node (ref "C170") (pin "1") (pinfunction "1_1") (pintype "passive"))
      (node (ref "C171") (pin "1") (pinfunction "1_1") (pintype "passive"))
      (node (ref "C172") (pin "1") (pinfunction "1_1") (pintype "passive"))
      (node (ref "C173") (pin "1") (pinfunction "1_1") (pintype "passive"))
      (node (ref "C174") (pin "1") (pinfunction "1_1") (pintype "passive"))
      (node (ref "C175") (pin "1") (pinfunction "1_1") (pintype "passive"))
      (node (ref "C176") (pin "1") (pinfunction "1_1") (pintype "passive"))
      (node (ref "C177") (pin "1") (pinfunction "1_1") (pintype "passive"))
      (node (ref "C178") (pin "1") (pinfunction "1_1") (pintype "passive"))
      (node (ref "C179") (pin "1") (pinfunction "1_1") (pintype "passive"))
      (node (ref "C180") (pin "1") (pinfunction "1_1") (pintype "passive"))
      (node (ref "C181") (pin "1") (pinfunction "1_1") (pintype "passive"))
      (node (ref "C182") (pin "1") (pinfunction "1_1") (pintype "passive"))
      (node (ref "C183") (pin "1") (pinfunction "1_1") (pintype "passive"))
      (node (ref "C184") (pin "1") (pinfunction "1_1") (pintype "passive"))
      (node (ref "C185") (pin "1") (pinfunction "1_1") (pintype "passive"))
      (node (ref "C186") (pin "1") (pinfunction "1_1") (pintype "passive"))
      (node (ref "C187") (pin "1") (pinfunction "1_1") (pintype "passive"))
      (node (ref "C188") (pin "1") (pinfunction "1_1") (pintype "passive"))
      (node (ref "C190") (pin "1") (pinfunction "1_1") (pintype "passive"))
      (node (ref "C191") (pin "1") (pinfunction "1_1") (pintype "passive"))
      (node (ref "C192") (pin "1") (pinfunction "1_1") (pintype "passive"))
      (node (ref "C193") (pin "1") (pinfunction "1_1") (pintype "passive"))
      (node (ref "C194") (pin "1") (pinfunction "1_1") (pintype "passive"))
      (node (ref "C195") (pin "1") (pinfunction "1_1") (pintype "passive"))
      (node (ref "C196") (pin "1") (pinfunction "1_1") (pintype "passive"))
      (node (ref "C199") (pin "1") (pinfunction "1_1") (pintype "passive"))
      (node (ref "C201") (pin "1") (pinfunction "1_1") (pintype "passive"))
      (node (ref "C203") (pin "1") (pinfunction "1_1") (pintype "passive"))
      (node (ref "C204") (pin "1") (pinfunction "1_1") (pintype "passive"))
      (node (ref "C205") (pin "1") (pinfunction "1_1") (pintype "passive"))
      (node (ref "C206") (pin "1") (pinfunction "1_1") (pintype "passive"))
      (node (ref "C207") (pin "1") (pinfunction "1_1") (pintype "passive"))
      (node (ref "C208") (pin "1") (pinfunction "1_1") (pintype "passive"))
      (node (ref "C209") (pin "1") (pinfunction "1_1") (pintype "passive"))
      (node (ref "C210") (pin "1") (pinfunction "1_1") (pintype "passive"))
      (node (ref "C211") (pin "1") (pinfunction "1_1") (pintype "passive"))
      (node (ref "C212") (pin "1") (pinfunction "1_1") (pintype "passive"))
      (node (ref "C213") (pin "1") (pinfunction "1_1") (pintype "passive"))
      (node (ref "C214") (pin "1") (pinfunction "1_1") (pintype "passive"))
      (node (ref "C215") (pin "1") (pinfunction "1_1") (pintype "passive"))
      (node (ref "C216") (pin "1") (pinfunction "1_1") (pintype "passive"))
      (node (ref "C217") (pin "1") (pinfunction "1_1") (pintype "passive"))
      (node (ref "C218") (pin "1") (pinfunction "1_1") (pintype "passive"))
      (node (ref "C219") (pin "1") (pinfunction "1_1") (pintype "passive"))
      (node (ref "C220") (pin "1") (pinfunction "1_1") (pintype "passive"))
      (node (ref "C221") (pin "1") (pinfunction "1_1") (pintype "passive"))
      (node (ref "C222") (pin "1") (pinfunction "1_1") (pintype "passive"))
      (node (ref "C223") (pin "1") (pinfunction "1_1") (pintype "passive"))
      (node (ref "C418") (pin "1") (pinfunction "1_1") (pintype "passive"))
      (node (ref "C419") (pin "1") (pinfunction "1_1") (pintype "passive"))
      (node (ref "C420") (pin "1") (pinfunction "1_1") (pintype "passive"))
      (node (ref "C422") (pin "1") (pinfunction "1_1") (pintype "passive"))
      (node (ref "C423") (pin "1") (pinfunction "1_1") (pintype "passive"))
      (node (ref "C424") (pin "1") (pinfunction "1_1") (pintype "passive"))
      (node (ref "C425") (pin "1") (pinfunction "1_1") (pintype "passive"))
      (node (ref "C426") (pin "1") (pinfunction "1_1") (pintype "passive"))
      (node (ref "C427") (pin "1") (pinfunction "1_1") (pintype "passive"))
      (node (ref "C429") (pin "1") (pinfunction "1_1") (pintype "passive"))
      (node (ref "C431") (pin "1") (pinfunction "1_1") (pintype "passive"))
      (node (ref "C432") (pin "1") (pinfunction "1_1") (pintype "passive"))
      (node (ref "C433") (pin "1") (pinfunction "1_1") (pintype "passive"))
      (node (ref "C435") (pin "1") (pinfunction "1_1") (pintype "passive"))
      (node (ref "C436") (pin "1") (pinfunction "1_1") (pintype "passive"))
      (node (ref "U50") (pin "A11") (pinfunction "GND_A11") (pintype "passive"))
      (node (ref "U50") (pin "A12") (pinfunction "GND_A12") (pintype "passive"))
      (node (ref "U50") (pin "A2") (pinfunction "GND_A2") (pintype "passive"))
      (node (ref "U50") (pin "A22") (pinfunction "GND_A22") (pintype "passive"))
      (node (ref "U50") (pin "A3") (pinfunction "GND_A3") (pintype "passive"))
      (node (ref "U50") (pin "A5") (pinfunction "GND_A5") (pintype "passive"))
      (node (ref "U50") (pin "A7") (pinfunction "GND_A7") (pintype "passive"))
      (node (ref "U50") (pin "A9") (pinfunction "GND_A9") (pintype "passive"))
      (node (ref "U50") (pin "AA12") (pinfunction "GND_AA12") (pintype "passive"))
      (node (ref "U50") (pin "AA2") (pinfunction "GND_AA2") (pintype "passive"))
      (node (ref "U50") (pin "AA22") (pinfunction "GND_AA22") (pintype "passive"))
      (node (ref "U50") (pin "AB19") (pinfunction "GND_AB19") (pintype "passive"))
      (node (ref "U50") (pin "AB9") (pinfunction "GND_AB9") (pintype "passive"))
      (node (ref "U50") (pin "B12") (pinfunction "GND_B12") (pintype "passive"))
      (node (ref "U50") (pin "B19") (pinfunction "GND_B19") (pintype "passive"))
      (node (ref "U50") (pin "B3") (pinfunction "GND_B3") (pintype "passive"))
      (node (ref "U50") (pin "C10") (pinfunction "GND_C10") (pintype "passive"))
      (node (ref "U50") (pin "C12") (pinfunction "GND_C12") (pintype "passive"))
      (node (ref "U50") (pin "C16") (pinfunction "GND_C16") (pintype "passive"))
      (node (ref "U50") (pin "C3") (pinfunction "GND_C3") (pintype "passive"))
      (node (ref "U50") (pin "C6") (pinfunction "GND_C6") (pintype "passive"))
      (node (ref "U50") (pin "D12") (pinfunction "GND_D12") (pintype "passive"))
      (node (ref "U50") (pin "D13") (pinfunction "GND_D13") (pintype "passive"))
      (node (ref "U50") (pin "D3") (pinfunction "GND_D3") (pintype "passive"))
      (node (ref "U50") (pin "D4") (pinfunction "GND_D4") (pintype "passive"))
      (node (ref "U50") (pin "D8") (pinfunction "GND_D8") (pintype "passive"))
      (node (ref "U50") (pin "E11") (pinfunction "GND_E11") (pintype "passive"))
      (node (ref "U50") (pin "E20") (pinfunction "GND_E20") (pintype "passive"))
      (node (ref "U50") (pin "E4") (pinfunction "GND_E4") (pintype "passive"))
      (node (ref "U50") (pin "E5") (pinfunction "GND_E5") (pintype "passive"))
      (node (ref "U50") (pin "E7") (pinfunction "GND_E7") (pintype "passive"))
      (node (ref "U50") (pin "E9") (pinfunction "GND_E9") (pintype "passive"))
      (node (ref "U50") (pin "F11") (pinfunction "GND_F11") (pintype "passive"))
      (node (ref "U50") (pin "F17") (pinfunction "GND_F17") (pintype "passive"))
      (node (ref "U50") (pin "F5") (pinfunction "GND_F5") (pintype "passive"))
      (node (ref "U50") (pin "G10") (pinfunction "GND_G10") (pintype "passive"))
      (node (ref "U50") (pin "G12") (pinfunction "GND_G12") (pintype "passive"))
      (node (ref "U50") (pin "G14") (pinfunction "GND_G14") (pintype "passive"))
      (node (ref "U50") (pin "G5") (pinfunction "GND_G5") (pintype "passive"))
      (node (ref "U50") (pin "G6") (pinfunction "GND_G6") (pintype "passive"))
      (node (ref "U50") (pin "G7") (pinfunction "GND_G7") (pintype "passive"))
      (node (ref "U50") (pin "G8") (pinfunction "GND_G8") (pintype "passive"))
      (node (ref "U50") (pin "G9") (pinfunction "GND_G9") (pintype "passive"))
      (node (ref "U50") (pin "H1") (pinfunction "GND_H1") (pintype "passive"))
      (node (ref "U50") (pin "H11") (pinfunction "GND_H11") (pintype "passive"))
      (node (ref "U50") (pin "H21") (pinfunction "GND_H21") (pintype "passive"))
      (node (ref "U50") (pin "H7") (pinfunction "GND_H7") (pintype "passive"))
      (node (ref "U50") (pin "H9") (pinfunction "GND_H9") (pintype "passive"))
      (node (ref "U50") (pin "J10") (pinfunction "GND_J10") (pintype "passive"))
      (node (ref "U50") (pin "J12") (pinfunction "GND_J12") (pintype "passive"))
      (node (ref "U50") (pin "J18") (pinfunction "GND_J18") (pintype "passive"))
      (node (ref "U50") (pin "J8") (pinfunction "GND_J8") (pintype "passive"))
      (node (ref "U50") (pin "K11") (pinfunction "GND_K11") (pintype "passive"))
      (node (ref "U50") (pin "K15") (pinfunction "GND_K15") (pintype "passive"))
      (node (ref "U50") (pin "K5") (pinfunction "GND_K5") (pintype "passive"))
      (node (ref "U50") (pin "K7") (pinfunction "GND_K7") (pintype "passive"))
      (node (ref "U50") (pin "L2") (pinfunction "GND_L2") (pintype "passive"))
      (node (ref "U50") (pin "L22") (pinfunction "GND_L22") (pintype "passive"))
      (node (ref "U50") (pin "L8") (pinfunction "GND_L8") (pintype "passive"))
      (node (ref "U50") (pin "M11") (pinfunction "GND_M11") (pintype "passive"))
      (node (ref "U50") (pin "M19") (pinfunction "GND_M19") (pintype "passive"))
      (node (ref "U50") (pin "M7") (pinfunction "GND_M7") (pintype "passive"))
      (node (ref "U50") (pin "N16") (pinfunction "GND_N16") (pintype "passive"))
      (node (ref "U50") (pin "N6") (pinfunction "GND_N6") (pintype "passive"))
      (node (ref "U50") (pin "N8") (pinfunction "GND_N8") (pintype "passive"))
      (node (ref "U50") (pin "P11") (pinfunction "GND_P11") (pintype "passive"))
      (node (ref "U50") (pin "P13") (pinfunction "GND_P13") (pintype "passive"))
      (node (ref "U50") (pin "P3") (pinfunction "GND_P3") (pintype "passive"))
      (node (ref "U50") (pin "P7") (pinfunction "GND_P7") (pintype "passive"))
      (node (ref "U50") (pin "P9") (pinfunction "GND_P9") (pintype "passive"))
      (node (ref "U50") (pin "R10") (pinfunction "GND_R10") (pintype "passive"))
      (node (ref "U50") (pin "R12") (pinfunction "GND_R12") (pintype "passive"))
      (node (ref "U50") (pin "R20") (pinfunction "GND_R20") (pintype "passive"))
      (node (ref "U50") (pin "R8") (pinfunction "GND_R8") (pintype "passive"))
      (node (ref "U50") (pin "T11") (pinfunction "GND_T11") (pintype "passive"))
      (node (ref "U50") (pin "T17") (pinfunction "GND_T17") (pintype "passive"))
      (node (ref "U50") (pin "T7") (pinfunction "GND_T7") (pintype "passive"))
      (node (ref "U50") (pin "T9") (pinfunction "GND_T9") (pintype "passive"))
      (node (ref "U50") (pin "U14") (pinfunction "GND_U14") (pintype "passive"))
      (node (ref "U50") (pin "U4") (pinfunction "GND_U4") (pintype "passive"))
      (node (ref "U50") (pin "V1") (pinfunction "GND_V1") (pintype "passive"))
      (node (ref "U50") (pin "V11") (pinfunction "GND_V11") (pintype "passive"))
      (node (ref "U50") (pin "V21") (pinfunction "GND_V21") (pintype "passive"))
      (node (ref "U50") (pin "W18") (pinfunction "GND_W18") (pintype "passive"))
      (node (ref "U50") (pin "W8") (pinfunction "GND_W8") (pintype "passive"))
      (node (ref "U50") (pin "Y15") (pinfunction "GND_Y15") (pintype "passive"))
      (node (ref "U50") (pin "Y5") (pinfunction "GND_Y5") (pintype "passive"))
    )
    (net (code "4") (name "VCCAUX_1V8") (class "Default")
      (node (ref "C166") (pin "2") (pinfunction "2_2") (pintype "passive"))
      (node (ref "C167") (pin "2") (pinfunction "2_2") (pintype "passive"))
      (node (ref "C168") (pin "2") (pinfunction "2_2") (pintype "passive"))
      (node (ref "C170") (pin "2") (pinfunction "2_2") (pintype "passive"))
      (node (ref "C190") (pin "2") (pinfunction "2_2") (pintype "passive"))
      (node (ref "C191") (pin "2") (pinfunction "2_2") (pintype "passive"))
      (node (ref "C192") (pin "2") (pinfunction "2_2") (pintype "passive"))
      (node (ref "C193") (pin "2") (pinfunction "2_2") (pintype "passive"))
      (node (ref "C194") (pin "2") (pinfunction "2_2") (pintype "passive"))
      (node (ref "C195") (pin "2") (pinfunction "2_2") (pintype "passive"))
      (node (ref "C196") (pin "2") (pinfunction "2_2") (pintype "passive"))
      (node (ref "C199") (pin "2") (pinfunction "2_2") (pintype "passive"))
      (node (ref "C206") (pin "2") (pinfunction "2_2") (pintype "passive"))
      (node (ref "C207") (pin "2") (pinfunction "2_2") (pintype "passive"))
      (node (ref "C208") (pin "2") (pinfunction "2_2") (pintype "passive"))
      (node (ref "C209") (pin "2") (pinfunction "2_2") (pintype "passive"))
      (node (ref "C216") (pin "2") (pinfunction "2_2") (pintype "passive"))
      (node (ref "C220") (pin "2") (pinfunction "2_2") (pintype "passive"))
      (node (ref "C221") (pin "2") (pinfunction "2_2") (pintype "passive"))
      (node (ref "C419") (pin "2") (pinfunction "2_2") (pintype "passive"))
      (node (ref "C420") (pin "2") (pinfunction "2_2") (pintype "passive"))
      (node (ref "C422") (pin "2") (pinfunction "2_2") (pintype "passive"))
      (node (ref "C423") (pin "2") (pinfunction "2_2") (pintype "passive"))
      (node (ref "C424") (pin "2") (pinfunction "2_2") (pintype "passive"))
      (node (ref "C425") (pin "2") (pinfunction "2_2") (pintype "passive"))
      (node (ref "C426") (pin "2") (pinfunction "2_2") (pintype "passive"))
      (node (ref "C427") (pin "2") (pinfunction "2_2") (pintype "passive"))
      (node (ref "R255") (pin "1") (pinfunction "1_1") (pintype "passive"))
      (node (ref "U50") (pin "A17") (pinfunction "VCCO_16_A17") (pintype "passive"))
      (node (ref "U50") (pin "B14") (pinfunction "VCCO_16_B14") (pintype "passive"))
      (node (ref "U50") (pin "C21") (pinfunction "VCCO_16_C21") (pintype "passive"))
      (node (ref "U50") (pin "D18") (pinfunction "VCCO_16_D18") (pintype "passive"))
      (node (ref "U50") (pin "E15") (pinfunction "VCCO_16_E15") (pintype "passive"))
      (node (ref "U50") (pin "F22") (pinfunction "VCCO_16_F22") (pintype "passive"))
      (node (ref "U50") (pin "G19") (pinfunction "VCCO_15_G19") (pintype "passive"))
      (node (ref "U50") (pin "H12") (pinfunction "VCCAUX_H12") (pintype "passive"))
      (node (ref "U50") (pin "H16") (pinfunction "VCCO_15_H16") (pintype "passive"))
      (node (ref "U50") (pin "J13") (pinfunction "VCCO_15_J13") (pintype "passive"))
      (node (ref "U50") (pin "K12") (pinfunction "VCCAUX_K12") (pintype "passive"))
      (node (ref "U50") (pin "K20") (pinfunction "VCCO_15_K20") (pintype "passive"))
      (node (ref "U50") (pin "L17") (pinfunction "VCCO_15_L17") (pintype "passive"))
      (node (ref "U50") (pin "M12") (pinfunction "VCCAUX_M12") (pintype "passive"))
      (node (ref "U50") (pin "N21") (pinfunction "VCCO_15_N21") (pintype "passive"))
      (node (ref "U50") (pin "P12") (pinfunction "VCCAUX_P12") (pintype "passive"))
      (node (ref "U50") (pin "R11") (pinfunction "VCCAUX_R11") (pintype "passive"))
    )
    (net (code "5") (name "VCCBRAM_1V0") (class "Default")
      (node (ref "C114") (pin "1") (pinfunction "1_1") (pintype "passive"))
      (node (ref "C137") (pin "2") (pinfunction "2_2") (pintype "passive"))
      (node (ref "C138") (pin "2") (pinfunction "2_2") (pintype "passive"))
      (node (ref "C139") (pin "2") (pinfunction "2_2") (pintype "passive"))
      (node (ref "C140") (pin "2") (pinfunction "2_2") (pintype "passive"))
      (node (ref "C141") (pin "2") (pinfunction "2_2") (pintype "passive"))
      (node (ref "C142") (pin "2") (pinfunction "2_2") (pintype "passive"))
      (node (ref "C143") (pin "2") (pinfunction "2_2") (pintype "passive"))
      (node (ref "C144") (pin "2") (pinfunction "2_2") (pintype "passive"))
      (node (ref "C145") (pin "2") (pinfunction "2_2") (pintype "passive"))
      (node (ref "C146") (pin "2") (pinfunction "2_2") (pintype "passive"))
      (node (ref "C147") (pin "2") (pinfunction "2_2") (pintype "passive"))
      (node (ref "C148") (pin "2") (pinfunction "2_2") (pintype "passive"))
      (node (ref "C149") (pin "2") (pinfunction "2_2") (pintype "passive"))
      (node (ref "C150") (pin "2") (pinfunction "2_2") (pintype "passive"))
      (node (ref "C152") (pin "2") (pinfunction "2_2") (pintype "passive"))
      (node (ref "C153") (pin "2") (pinfunction "2_2") (pintype "passive"))
      (node (ref "C154") (pin "2") (pinfunction "2_2") (pintype "passive"))
      (node (ref "C155") (pin "2") (pinfunction "2_2") (pintype "passive"))
      (node (ref "C158") (pin "2") (pinfunction "2_2") (pintype "passive"))
      (node (ref "C159") (pin "2") (pinfunction "2_2") (pintype "passive"))
      (node (ref "C160") (pin "2") (pinfunction "2_2") (pintype "passive"))
      (node (ref "C161") (pin "2") (pinfunction "2_2") (pintype "passive"))
      (node (ref "C162") (pin "2") (pinfunction "2_2") (pintype "passive"))
      (node (ref "C163") (pin "2") (pinfunction "2_2") (pintype "passive"))
      (node (ref "C164") (pin "2") (pinfunction "2_2") (pintype "passive"))
      (node (ref "C171") (pin "2") (pinfunction "2_2") (pintype "passive"))
      (node (ref "C172") (pin "2") (pinfunction "2_2") (pintype "passive"))
      (node (ref "C173") (pin "2") (pinfunction "2_2") (pintype "passive"))
      (node (ref "C201") (pin "2") (pinfunction "2_2") (pintype "passive"))
      (node (ref "C418") (pin "2") (pinfunction "2_2") (pintype "passive"))
      (node (ref "U50") (pin "H10") (pinfunction "VCCINT_H10") (pintype "passive"))
      (node (ref "U50") (pin "H8") (pinfunction "VCCINT_H8") (pintype "passive"))
      (node (ref "U50") (pin "J11") (pinfunction "VCCBRAM_J11") (pintype "passive"))
      (node (ref "U50") (pin "J7") (pinfunction "VCCINT_J7") (pintype "passive"))
      (node (ref "U50") (pin "J9") (pinfunction "VCCINT_J9") (pintype "passive"))
      (node (ref "U50") (pin "K8") (pinfunction "VCCINT_K8") (pintype "passive"))
      (node (ref "U50") (pin "L11") (pinfunction "VCCBRAM_L11") (pintype "passive"))
      (node (ref "U50") (pin "L7") (pinfunction "VCCINT_L7") (pintype "passive"))
      (node (ref "U50") (pin "M8") (pinfunction "VCCINT_M8") (pintype "passive"))
      (node (ref "U50") (pin "N11") (pinfunction "VCCBRAM_N11") (pintype "passive"))
      (node (ref "U50") (pin "N7") (pinfunction "VCCINT_N7") (pintype "passive"))
      (node (ref "U50") (pin "P10") (pinfunction "VCCINT_P10") (pintype "passive"))
      (node (ref "U50") (pin "P8") (pinfunction "VCCINT_P8") (pintype "passive"))
      (node (ref "U50") (pin "R7") (pinfunction "VCCINT_R7") (pintype "passive"))
      (node (ref "U50") (pin "R9") (pinfunction "VCCINT_R9") (pintype "passive"))
      (node (ref "U50") (pin "T10") (pinfunction "VCCINT_T10") (pintype "passive"))
      (node (ref "U50") (pin "T8") (pinfunction "VCCINT_T8") (pintype "passive"))
    )
    (net (code "6") (name "VCC_1V5") (class "Default")
      (node (ref "R257") (pin "2") (pinfunction "2_2") (pintype "passive"))
    )
    (net (code "7") (name "VCC_1V8") (class "Default")
      (node (ref "R255") (pin "2") (pinfunction "2_2") (pintype "passive"))
    )
    (net (code "8") (name "VCC_3V3") (class "Default")
      (node (ref "R256") (pin "2") (pinfunction "2_2") (pintype "passive"))
    )
  )
)
